# Interlock.net
KiCad netlist of a schematic drawn in EAGLE
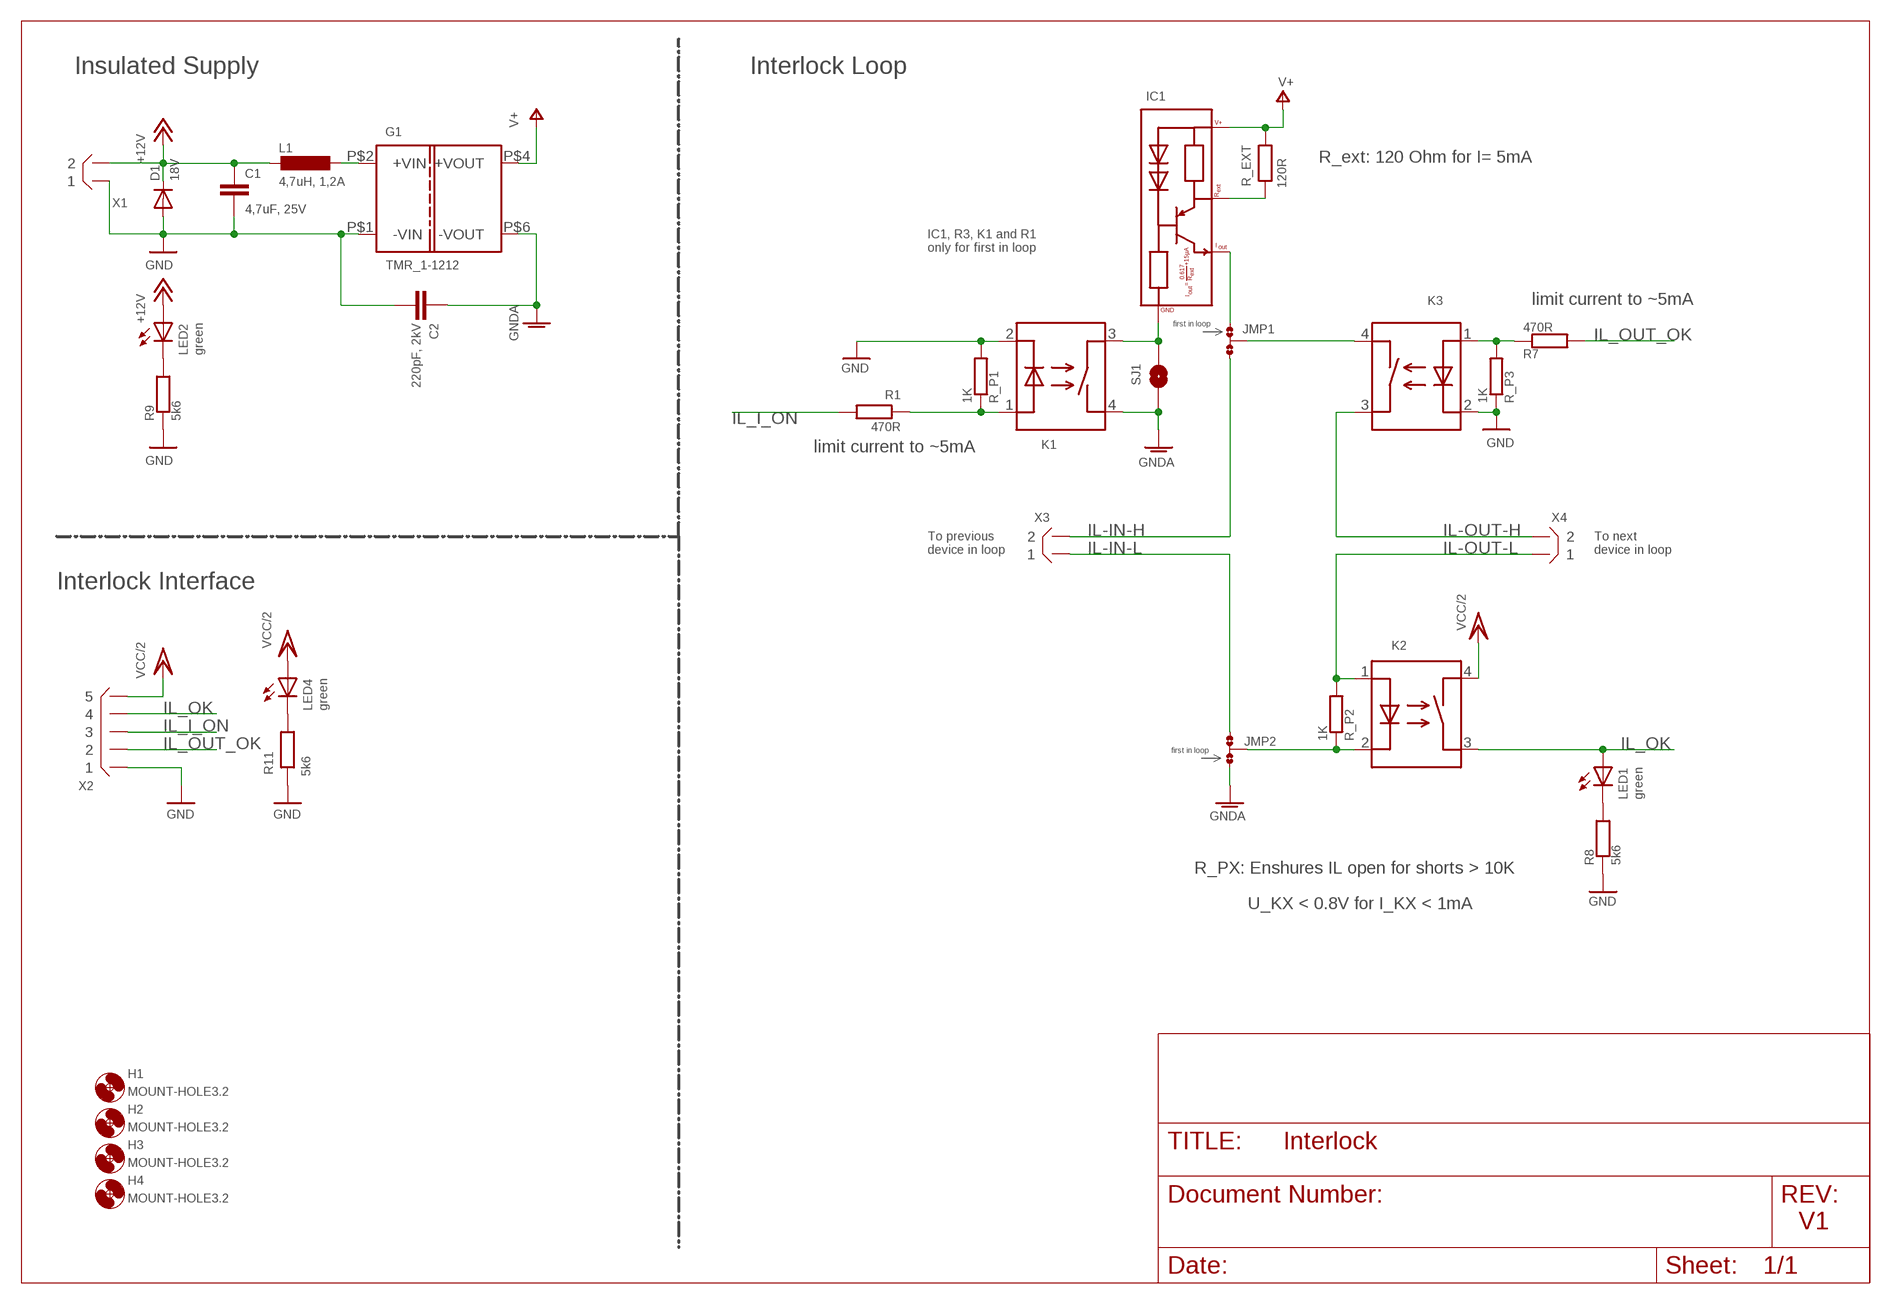
[diagram p0: schematic, sheet 1]

(export (version "E")
  (design (tool "Eeschema 10.0.6"))
  (components
    (comp (ref "C1")
      (value "4,7uF, 25V")
      (footprint "eagle-import:C0805")
      (libsource (lib "eagle-import") (part "C-EUC0805"))
    )
    (comp (ref "C2")
      (value "220pF, 2kV")
      (footprint "eagle-import:C1210_HV")
      (libsource (lib "eagle-import") (part "CC1210_HV"))
    )
    (comp (ref "D1")
      (value "18V")
      (footprint "eagle-import:DO214AA")
      (libsource (lib "eagle-import") (part "DIODE-DO214AA"))
    )
    (comp (ref "G1")
      (value "TMR_1-1212")
      (footprint "eagle-import:TMR_1-__1_")
      (libsource (lib "eagle-import") (part "TMR_1-??1?"))
    )
    (comp (ref "H1")
      (value "MOUNT-HOLE3.2")
      (footprint "eagle-import:3,2")
      (libsource (lib "eagle-import") (part "MOUNT-HOLE3.2"))
    )
    (comp (ref "H2")
      (value "MOUNT-HOLE3.2")
      (footprint "eagle-import:3,2")
      (libsource (lib "eagle-import") (part "MOUNT-HOLE3.2"))
    )
    (comp (ref "H3")
      (value "MOUNT-HOLE3.2")
      (footprint "eagle-import:3,2")
      (libsource (lib "eagle-import") (part "MOUNT-HOLE3.2"))
    )
    (comp (ref "H4")
      (value "MOUNT-HOLE3.2")
      (footprint "eagle-import:3,2")
      (libsource (lib "eagle-import") (part "MOUNT-HOLE3.2"))
    )
    (comp (ref "IC1")
      (value "PSSI2021SAY")
      (footprint "eagle-import:SOT353")
      (libsource (lib "eagle-import") (part "PSSI2021SAY"))
    )
    (comp (ref "JMP1")
      (value "0R-JUMPA")
      (footprint "eagle-import:A0R-JMP")
      (libsource (lib "eagle-import") (part "0R-JUMPA"))
    )
    (comp (ref "JMP2")
      (value "0R-JUMPA")
      (footprint "eagle-import:A0R-JMP")
      (libsource (lib "eagle-import") (part "0R-JUMPA"))
    )
    (comp (ref "K1")
      (value "ASSR-1218")
      (footprint "eagle-import:SO-4")
      (libsource (lib "eagle-import") (part "ASSR-1218"))
    )
    (comp (ref "K2")
      (value "ASSR-1218")
      (footprint "eagle-import:SO-4")
      (libsource (lib "eagle-import") (part "ASSR-1218"))
    )
    (comp (ref "K3")
      (value "ASSR-1218")
      (footprint "eagle-import:SO-4")
      (libsource (lib "eagle-import") (part "ASSR-1218"))
    )
    (comp (ref "L1")
      (value "4,7uH, 1,2A")
      (footprint "eagle-import:L3225M")
      (libsource (lib "eagle-import") (part "L-EUL3225M"))
    )
    (comp (ref "LED1")
      (value "green")
      (footprint "eagle-import:CHIPLED_0805")
      (libsource (lib "eagle-import") (part "LEDCHIPLED_0805"))
    )
    (comp (ref "LED2")
      (value "green")
      (footprint "eagle-import:CHIPLED_0805")
      (libsource (lib "eagle-import") (part "LEDCHIPLED_0805"))
    )
    (comp (ref "LED4")
      (value "green")
      (footprint "eagle-import:CHIPLED_0805")
      (libsource (lib "eagle-import") (part "LEDCHIPLED_0805"))
    )
    (comp (ref "R1")
      (value "470R")
      (footprint "eagle-import:R0805")
      (libsource (lib "eagle-import") (part "R"))
    )
    (comp (ref "R7")
      (value "470R")
      (footprint "eagle-import:R0805")
      (libsource (lib "eagle-import") (part "R"))
    )
    (comp (ref "R8")
      (value "5k6")
      (footprint "eagle-import:R0805")
      (libsource (lib "eagle-import") (part "R"))
    )
    (comp (ref "R9")
      (value "5k6")
      (footprint "eagle-import:R0805")
      (libsource (lib "eagle-import") (part "R"))
    )
    (comp (ref "R11")
      (value "5k6")
      (footprint "eagle-import:R0805")
      (libsource (lib "eagle-import") (part "R"))
    )
    (comp (ref "R_EXT")
      (value "120R")
      (footprint "eagle-import:R0805")
      (libsource (lib "eagle-import") (part "R"))
    )
    (comp (ref "R_P1")
      (value "1K")
      (footprint "eagle-import:R0603")
      (libsource (lib "eagle-import") (part "R0603"))
    )
    (comp (ref "R_P2")
      (value "1K")
      (footprint "eagle-import:R0603")
      (libsource (lib "eagle-import") (part "R0603"))
    )
    (comp (ref "R_P3")
      (value "1K")
      (footprint "eagle-import:R0603")
      (libsource (lib "eagle-import") (part "R0603"))
    )
    (comp (ref "SJ1")
      (value "SOLDERJUMPERNO")
      (footprint "eagle-import:SJ_2S-NO")
      (libsource (lib "eagle-import") (part "SOLDERJUMPERNO"))
    )
    (comp (ref "X1")
      (value "B2B-XH")
      (footprint "eagle-import:B2B-XH")
      (libsource (lib "eagle-import") (part "?2B-XHB"))
    )
    (comp (ref "X2")
      (value "B5B-XH")
      (footprint "eagle-import:B5B-XH")
      (libsource (lib "eagle-import") (part "?5B-XHB"))
    )
    (comp (ref "X3")
      (value "B2B-XH")
      (footprint "eagle-import:B2B-XH")
      (libsource (lib "eagle-import") (part "?2B-XHB"))
    )
    (comp (ref "X4")
      (value "B2B-XH")
      (footprint "eagle-import:B2B-XH")
      (libsource (lib "eagle-import") (part "?2B-XHB"))
    )
  )
  (nets
    (net (code "1") (name "+12V") (class "Default")
      (node (ref "C1") (pin "1") (pinfunction "1_1") (pintype "passive"))
      (node (ref "D1") (pin "C") (pinfunction "C_C") (pintype "passive"))
      (node (ref "L1") (pin "2") (pinfunction "2_2") (pintype "passive"))
      (node (ref "LED2") (pin "A") (pinfunction "A_A") (pintype "passive"))
      (node (ref "X1") (pin "P$2") (pinfunction "2_P$2") (pintype "bidirectional"))
    )
    (net (code "2") (name "/IL-IN-H") (class "Default")
      (node (ref "JMP1") (pin "3") (pinfunction "3_3") (pintype "passive"))
      (node (ref "X3") (pin "P$2") (pinfunction "2_P$2") (pintype "bidirectional"))
    )
    (net (code "3") (name "/IL-IN-L") (class "Default")
      (node (ref "JMP2") (pin "3") (pinfunction "3_3") (pintype "passive"))
      (node (ref "X3") (pin "P$1") (pinfunction "1_P$1") (pintype "bidirectional"))
    )
    (net (code "4") (name "/IL-OUT-H") (class "Default")
      (node (ref "K3") (pin "3") (pinfunction "O2_3") (pintype "bidirectional"))
      (node (ref "X4") (pin "P$2") (pinfunction "2_P$2") (pintype "bidirectional"))
    )
    (net (code "5") (name "/IL-OUT-L") (class "Default")
      (node (ref "K2") (pin "1") (pinfunction "I+_1") (pintype "bidirectional"))
      (node (ref "R_P2") (pin "2") (pinfunction "2_2") (pintype "passive"))
      (node (ref "X4") (pin "P$1") (pinfunction "1_P$1") (pintype "bidirectional"))
    )
    (net (code "6") (name "/IL_I_ON") (class "Default")
      (node (ref "R1") (pin "2") (pinfunction "2_2") (pintype "passive"))
      (node (ref "X2") (pin "P$3") (pinfunction "3_P$3") (pintype "bidirectional"))
    )
    (net (code "7") (name "/IL_OK") (class "Default")
      (node (ref "K2") (pin "3") (pinfunction "O2_3") (pintype "bidirectional"))
      (node (ref "LED1") (pin "A") (pinfunction "A_A") (pintype "passive"))
      (node (ref "X2") (pin "P$4") (pinfunction "4_P$4") (pintype "bidirectional"))
    )
    (net (code "8") (name "/IL_OUT_OK") (class "Default")
      (node (ref "R7") (pin "2") (pinfunction "2_2") (pintype "passive"))
      (node (ref "X2") (pin "P$2") (pinfunction "2_P$2") (pintype "bidirectional"))
    )
    (net (code "9") (name "GND") (class "Default")
      (node (ref "C1") (pin "2") (pinfunction "2_2") (pintype "passive"))
      (node (ref "C2") (pin "P$1") (pinfunction "1_P$1") (pintype "passive"))
      (node (ref "D1") (pin "A") (pinfunction "A_A") (pintype "passive"))
      (node (ref "G1") (pin "P$1") (pinfunction "-VIN_P$1") (pintype "bidirectional"))
      (node (ref "K1") (pin "2") (pinfunction "I-_2") (pintype "bidirectional"))
      (node (ref "K3") (pin "2") (pinfunction "I-_2") (pintype "bidirectional"))
      (node (ref "R11") (pin "1") (pinfunction "1_1") (pintype "passive"))
      (node (ref "R8") (pin "1") (pinfunction "1_1") (pintype "passive"))
      (node (ref "R9") (pin "1") (pinfunction "1_1") (pintype "passive"))
      (node (ref "R_P1") (pin "2") (pinfunction "2_2") (pintype "passive"))
      (node (ref "R_P3") (pin "1") (pinfunction "1_1") (pintype "passive"))
      (node (ref "X1") (pin "P$1") (pinfunction "1_P$1") (pintype "bidirectional"))
      (node (ref "X2") (pin "P$1") (pinfunction "1_P$1") (pintype "bidirectional"))
    )
    (net (code "10") (name "GNDA") (class "Default")
      (node (ref "C2") (pin "P$2") (pinfunction "2_P$2") (pintype "passive"))
      (node (ref "G1") (pin "P$6") (pinfunction "-VOUT_P$6") (pintype "bidirectional"))
      (node (ref "JMP2") (pin "1") (pinfunction "1_1") (pintype "passive"))
      (node (ref "K1") (pin "4") (pinfunction "O1_4") (pintype "bidirectional"))
      (node (ref "SJ1") (pin "1") (pinfunction "1_1") (pintype "passive"))
    )
    (net (code "11") (name "Net-(G1-+VIN)") (class "Default")
      (node (ref "G1") (pin "P$2") (pinfunction "+VIN_P$2") (pintype "bidirectional"))
      (node (ref "L1") (pin "1") (pinfunction "1_1") (pintype "passive"))
    )
    (net (code "12") (name "Net-(IC1-GND)") (class "Default")
      (node (ref "IC1") (pin "3") (pinfunction "GND_3") (pintype "bidirectional"))
      (node (ref "K1") (pin "3") (pinfunction "O2_3") (pintype "bidirectional"))
      (node (ref "SJ1") (pin "2") (pinfunction "2_2") (pintype "passive"))
    )
    (net (code "13") (name "Net-(IC1-IOUT)") (class "Default")
      (node (ref "IC1") (pin "2") (pinfunction "IOUT_2") (pintype "bidirectional"))
      (node (ref "JMP1") (pin "1") (pinfunction "1_1") (pintype "passive"))
    )
    (net (code "14") (name "Net-(IC1-REXT)") (class "Default")
      (node (ref "IC1") (pin "4") (pinfunction "REXT_4") (pintype "bidirectional"))
      (node (ref "R_EXT") (pin "1") (pinfunction "1_1") (pintype "passive"))
    )
    (net (code "15") (name "Net-(K1-I+)") (class "Default")
      (node (ref "K1") (pin "1") (pinfunction "I+_1") (pintype "bidirectional"))
      (node (ref "R1") (pin "1") (pinfunction "1_1") (pintype "passive"))
      (node (ref "R_P1") (pin "1") (pinfunction "1_1") (pintype "passive"))
    )
    (net (code "16") (name "Net-(K2-I-)") (class "Default")
      (node (ref "JMP2") (pin "2") (pinfunction "2_2") (pintype "passive"))
      (node (ref "K2") (pin "2") (pinfunction "I-_2") (pintype "bidirectional"))
      (node (ref "R_P2") (pin "1") (pinfunction "1_1") (pintype "passive"))
    )
    (net (code "17") (name "Net-(K3-I+)") (class "Default")
      (node (ref "K3") (pin "1") (pinfunction "I+_1") (pintype "bidirectional"))
      (node (ref "R7") (pin "1") (pinfunction "1_1") (pintype "passive"))
      (node (ref "R_P3") (pin "2") (pinfunction "2_2") (pintype "passive"))
    )
    (net (code "18") (name "Net-(K3-O1)") (class "Default")
      (node (ref "JMP1") (pin "2") (pinfunction "2_2") (pintype "passive"))
      (node (ref "K3") (pin "4") (pinfunction "O1_4") (pintype "bidirectional"))
    )
    (net (code "19") (name "Net-(LED1-PadC)") (class "Default")
      (node (ref "LED1") (pin "C") (pinfunction "C_C") (pintype "passive"))
      (node (ref "R8") (pin "2") (pinfunction "2_2") (pintype "passive"))
    )
    (net (code "20") (name "Net-(LED2-PadC)") (class "Default")
      (node (ref "LED2") (pin "C") (pinfunction "C_C") (pintype "passive"))
      (node (ref "R9") (pin "2") (pinfunction "2_2") (pintype "passive"))
    )
    (net (code "21") (name "Net-(LED4-PadC)") (class "Default")
      (node (ref "LED4") (pin "C") (pinfunction "C_C") (pintype "passive"))
      (node (ref "R11") (pin "2") (pinfunction "2_2") (pintype "passive"))
    )
    (net (code "22") (name "V+") (class "Default")
      (node (ref "G1") (pin "P$4") (pinfunction "+VOUT_P$4") (pintype "bidirectional"))
      (node (ref "IC1") (pin "5") (pinfunction "VSS_5") (pintype "bidirectional"))
      (node (ref "R_EXT") (pin "2") (pinfunction "2_2") (pintype "passive"))
    )
    (net (code "23") (name "VCC{slash}2") (class "Default")
      (node (ref "K2") (pin "4") (pinfunction "O1_4") (pintype "bidirectional"))
      (node (ref "LED4") (pin "A") (pinfunction "A_A") (pintype "passive"))
      (node (ref "X2") (pin "P$5") (pinfunction "5_P$5") (pintype "bidirectional"))
    )
  )
)
